# Large_Simon_Says.net
KiCad netlist of a schematic drawn in EAGLE
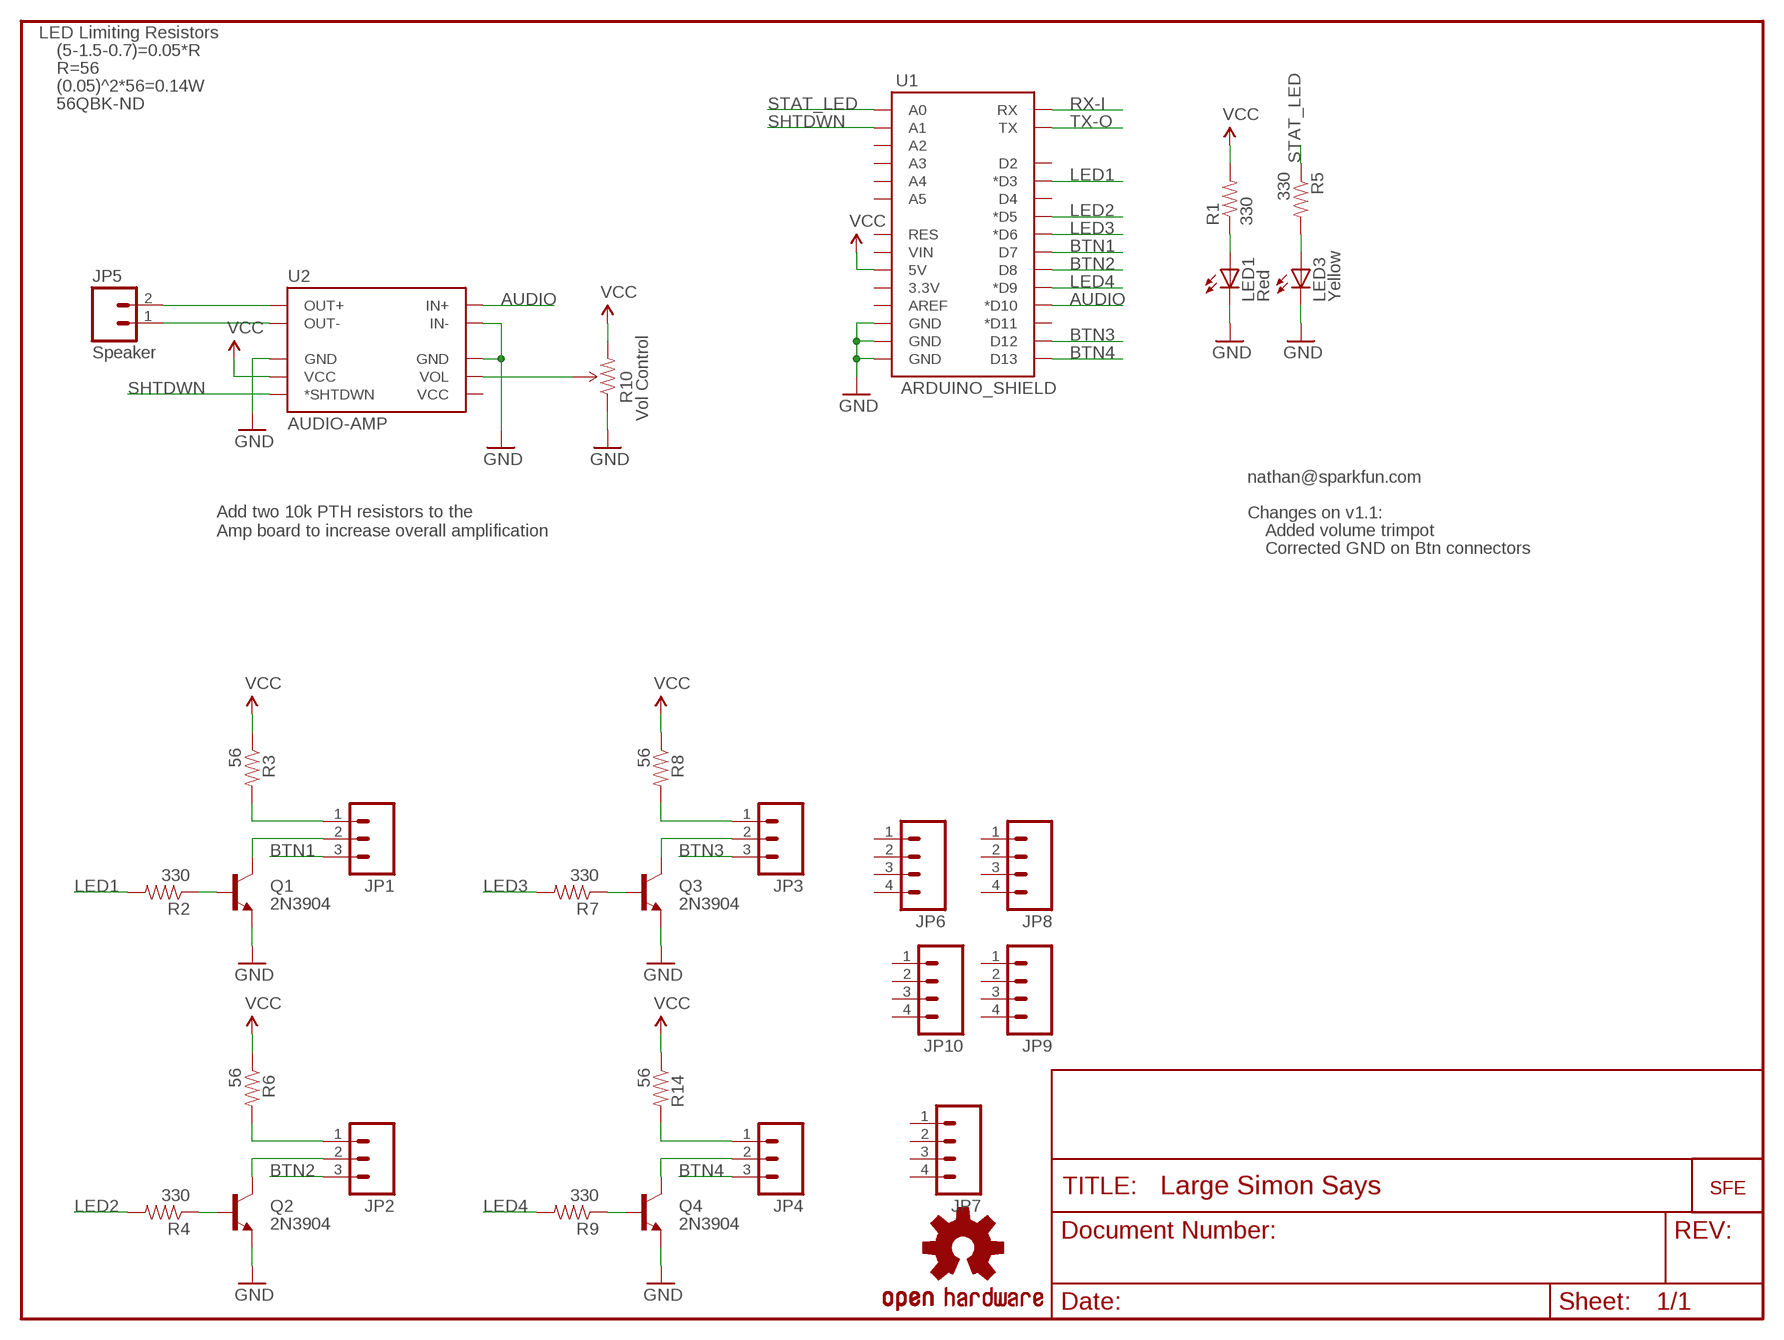
[diagram p0: schematic, sheet 1]

(export (version "E")
  (design (tool "Eeschema 10.0.6"))
  (components
    (comp (ref "JP1")
      (value "M03JST-PTH-VERT")
      (footprint "eagle-import:JST-3-PTH-VERT")
      (libsource (lib "eagle-import") (part "M03JST-PTH-VERT"))
    )
    (comp (ref "JP2")
      (value "M03JST-PTH-VERT")
      (footprint "eagle-import:JST-3-PTH-VERT")
      (libsource (lib "eagle-import") (part "M03JST-PTH-VERT"))
    )
    (comp (ref "JP3")
      (value "M03JST-PTH-VERT")
      (footprint "eagle-import:JST-3-PTH-VERT")
      (libsource (lib "eagle-import") (part "M03JST-PTH-VERT"))
    )
    (comp (ref "JP4")
      (value "M03JST-PTH-VERT")
      (footprint "eagle-import:JST-3-PTH-VERT")
      (libsource (lib "eagle-import") (part "M03JST-PTH-VERT"))
    )
    (comp (ref "JP5")
      (value "Speaker")
      (footprint "eagle-import:JST-2-PTH")
      (libsource (lib "eagle-import") (part "M02JST-PTH-2"))
    )
    (comp (ref "JP6")
      (value "M04JST-PTH")
      (footprint "eagle-import:JST-4-PTH")
      (libsource (lib "eagle-import") (part "M04JST-PTH"))
    )
    (comp (ref "JP7")
      (value "M04JST-PTH")
      (footprint "eagle-import:JST-4-PTH")
      (libsource (lib "eagle-import") (part "M04JST-PTH"))
    )
    (comp (ref "JP8")
      (value "M04JST-PTH")
      (footprint "eagle-import:JST-4-PTH")
      (libsource (lib "eagle-import") (part "M04JST-PTH"))
    )
    (comp (ref "JP9")
      (value "M04JST-PTH")
      (footprint "eagle-import:JST-4-PTH")
      (libsource (lib "eagle-import") (part "M04JST-PTH"))
    )
    (comp (ref "JP10")
      (value "M04JST-PTH")
      (footprint "eagle-import:JST-4-PTH")
      (libsource (lib "eagle-import") (part "M04JST-PTH"))
    )
    (comp (ref "LED1")
      (value "Red")
      (footprint "eagle-import:LED5MM")
      (libsource (lib "eagle-import") (part "LED5MM"))
    )
    (comp (ref "LED3")
      (value "Yellow")
      (footprint "eagle-import:LED5MM")
      (libsource (lib "eagle-import") (part "LED5MM"))
    )
    (comp (ref "Q1")
      (value "2N3904")
      (footprint "eagle-import:TO-92")
      (libsource (lib "eagle-import") (part "TRANSISTOR_NPNTO92"))
    )
    (comp (ref "Q2")
      (value "2N3904")
      (footprint "eagle-import:TO-92")
      (libsource (lib "eagle-import") (part "TRANSISTOR_NPNTO92"))
    )
    (comp (ref "Q3")
      (value "2N3904")
      (footprint "eagle-import:TO-92")
      (libsource (lib "eagle-import") (part "TRANSISTOR_NPNTO92"))
    )
    (comp (ref "Q4")
      (value "2N3904")
      (footprint "eagle-import:TO-92")
      (libsource (lib "eagle-import") (part "TRANSISTOR_NPNTO92"))
    )
    (comp (ref "R1")
      (value "330")
      (footprint "eagle-import:AXIAL-0.3")
      (libsource (lib "eagle-import") (part "RESISTORAXIAL-0.3"))
    )
    (comp (ref "R2")
      (value "330")
      (footprint "eagle-import:AXIAL-0.3")
      (libsource (lib "eagle-import") (part "RESISTORAXIAL-0.3"))
    )
    (comp (ref "R3")
      (value "56")
      (footprint "eagle-import:AXIAL-0.3")
      (libsource (lib "eagle-import") (part "RESISTORAXIAL-0.3"))
    )
    (comp (ref "R4")
      (value "330")
      (footprint "eagle-import:AXIAL-0.3")
      (libsource (lib "eagle-import") (part "RESISTORAXIAL-0.3"))
    )
    (comp (ref "R5")
      (value "330")
      (footprint "eagle-import:AXIAL-0.3")
      (libsource (lib "eagle-import") (part "RESISTORAXIAL-0.3"))
    )
    (comp (ref "R6")
      (value "56")
      (footprint "eagle-import:AXIAL-0.3")
      (libsource (lib "eagle-import") (part "RESISTORAXIAL-0.3"))
    )
    (comp (ref "R7")
      (value "330")
      (footprint "eagle-import:AXIAL-0.3")
      (libsource (lib "eagle-import") (part "RESISTORAXIAL-0.3"))
    )
    (comp (ref "R8")
      (value "56")
      (footprint "eagle-import:AXIAL-0.3")
      (libsource (lib "eagle-import") (part "RESISTORAXIAL-0.3"))
    )
    (comp (ref "R9")
      (value "330")
      (footprint "eagle-import:AXIAL-0.3")
      (libsource (lib "eagle-import") (part "RESISTORAXIAL-0.3"))
    )
    (comp (ref "R10")
      (value "Vol Control")
      (footprint "eagle-import:3386U")
      (libsource (lib "eagle-import") (part "TRIMPOT-PTH-KNOB"))
    )
    (comp (ref "R14")
      (value "56")
      (footprint "eagle-import:AXIAL-0.3")
      (libsource (lib "eagle-import") (part "RESISTORAXIAL-0.3"))
    )
    (comp (ref "U$1")
      (value "LOGO-SFENEW")
      (footprint "eagle-import:SFE-NEW-WEBLOGO")
      (libsource (lib "eagle-import") (part "LOGO-SFENEW"))
    )
    (comp (ref "U$3")
      (value "OSHW-LOGOS")
      (footprint "eagle-import:OSHW-LOGO-S")
      (libsource (lib "eagle-import") (part "OSHW-LOGOS"))
    )
    (comp (ref "U1")
      (value "ARDUINO_SHIELD")
      (footprint "eagle-import:DUEMILANOVE_SHIELD_NOHOLES")
      (libsource (lib "eagle-import") (part "ARDUINO_SHIELDNOHOLES"))
    )
    (comp (ref "U2")
      (value "AUDIO-AMP")
      (footprint "eagle-import:AUDIO-AMP-MONO")
      (libsource (lib "eagle-import") (part "AUDIO-AMP-MONODIP"))
    )
  )
  (nets
    (net (code "1") (name "/AUDIO") (class "Default")
      (node (ref "U1") (pin "D10") (pinfunction "*D10_D10") (pintype "bidirectional"))
      (node (ref "U2") (pin "IN+") (pinfunction "IN+_IN+") (pintype "bidirectional"))
    )
    (net (code "2") (name "/BTN1") (class "Default")
      (node (ref "JP1") (pin "3") (pinfunction "3_3") (pintype "passive"))
      (node (ref "U1") (pin "D7") (pinfunction "D7_D7") (pintype "bidirectional"))
    )
    (net (code "3") (name "/BTN2") (class "Default")
      (node (ref "JP2") (pin "3") (pinfunction "3_3") (pintype "passive"))
      (node (ref "U1") (pin "D8") (pinfunction "D8_D8") (pintype "bidirectional"))
    )
    (net (code "4") (name "/BTN3") (class "Default")
      (node (ref "JP3") (pin "3") (pinfunction "3_3") (pintype "passive"))
      (node (ref "U1") (pin "D12") (pinfunction "D12_D12") (pintype "bidirectional"))
    )
    (net (code "5") (name "/BTN4") (class "Default")
      (node (ref "JP4") (pin "3") (pinfunction "3_3") (pintype "passive"))
      (node (ref "U1") (pin "D13") (pinfunction "D13_D13") (pintype "bidirectional"))
    )
    (net (code "6") (name "/LED1") (class "Default")
      (node (ref "R2") (pin "P$2") (pinfunction "2_P$2") (pintype "passive"))
      (node (ref "U1") (pin "D3") (pinfunction "*D3_D3") (pintype "bidirectional"))
    )
    (net (code "7") (name "/LED2") (class "Default")
      (node (ref "R4") (pin "P$2") (pinfunction "2_P$2") (pintype "passive"))
      (node (ref "U1") (pin "D5") (pinfunction "*D5_D5") (pintype "bidirectional"))
    )
    (net (code "8") (name "/LED3") (class "Default")
      (node (ref "R7") (pin "P$2") (pinfunction "2_P$2") (pintype "passive"))
      (node (ref "U1") (pin "D6") (pinfunction "*D6_D6") (pintype "bidirectional"))
    )
    (net (code "9") (name "/LED4") (class "Default")
      (node (ref "R9") (pin "P$2") (pinfunction "2_P$2") (pintype "passive"))
      (node (ref "U1") (pin "D9") (pinfunction "*D9_D9") (pintype "bidirectional"))
    )
    (net (code "10") (name "/RX-I") (class "Default")
      (node (ref "U1") (pin "RX") (pinfunction "RX_RX") (pintype "bidirectional"))
    )
    (net (code "11") (name "/SHTDWN") (class "Default")
      (node (ref "U1") (pin "A1") (pinfunction "A1_A1") (pintype "bidirectional"))
      (node (ref "U2") (pin "S") (pinfunction "*SHTDWN_S") (pintype "bidirectional"))
    )
    (net (code "12") (name "/STAT_LED") (class "Default")
      (node (ref "R5") (pin "P$1") (pinfunction "1_P$1") (pintype "passive"))
      (node (ref "U1") (pin "A0") (pinfunction "A0_A0") (pintype "bidirectional"))
    )
    (net (code "13") (name "/TX-O") (class "Default")
      (node (ref "U1") (pin "TX") (pinfunction "TX_TX") (pintype "bidirectional"))
    )
    (net (code "14") (name "GND") (class "Default")
      (node (ref "LED1") (pin "K") (pinfunction "C_K") (pintype "passive"))
      (node (ref "LED3") (pin "K") (pinfunction "C_K") (pintype "passive"))
      (node (ref "Q1") (pin "1") (pinfunction "E_1") (pintype "passive"))
      (node (ref "Q2") (pin "1") (pinfunction "E_1") (pintype "passive"))
      (node (ref "Q3") (pin "1") (pinfunction "E_1") (pintype "passive"))
      (node (ref "Q4") (pin "1") (pinfunction "E_1") (pintype "passive"))
      (node (ref "R10") (pin "1") (pinfunction "CCW_1") (pintype "passive"))
      (node (ref "U1") (pin "GND@0") (pinfunction "GND_GND@0") (pintype "bidirectional"))
      (node (ref "U1") (pin "GND@1") (pinfunction "GND_GND@1") (pintype "bidirectional"))
      (node (ref "U1") (pin "GND@2") (pinfunction "GND_GND@2") (pintype "bidirectional"))
      (node (ref "U2") (pin "IN-") (pinfunction "IN-_IN-") (pintype "bidirectional"))
      (node (ref "U2") (pin "PWR-") (pinfunction "GND_PWR-") (pintype "bidirectional"))
      (node (ref "U2") (pin "VOL-") (pinfunction "GND_VOL-") (pintype "bidirectional"))
    )
    (net (code "15") (name "Net-(JP5-Pad1)") (class "Default")
      (node (ref "JP5") (pin "1") (pinfunction "1_1") (pintype "passive"))
      (node (ref "U2") (pin "OUT-") (pinfunction "OUT-_OUT-") (pintype "bidirectional"))
    )
    (net (code "16") (name "Net-(JP5-Pad2)") (class "Default")
      (node (ref "JP5") (pin "2") (pinfunction "2_2") (pintype "passive"))
      (node (ref "U2") (pin "OUT+") (pinfunction "OUT+_OUT+") (pintype "bidirectional"))
    )
    (net (code "17") (name "Net-(Q1-B)") (class "Default")
      (node (ref "Q1") (pin "2") (pinfunction "B_2") (pintype "passive"))
      (node (ref "R2") (pin "P$1") (pinfunction "1_P$1") (pintype "passive"))
    )
    (net (code "18") (name "Net-(Q1-C)") (class "Default")
      (node (ref "JP1") (pin "2") (pinfunction "2_2") (pintype "passive"))
      (node (ref "Q1") (pin "3") (pinfunction "C_3") (pintype "passive"))
    )
    (net (code "19") (name "Net-(Q2-B)") (class "Default")
      (node (ref "Q2") (pin "2") (pinfunction "B_2") (pintype "passive"))
      (node (ref "R4") (pin "P$1") (pinfunction "1_P$1") (pintype "passive"))
    )
    (net (code "20") (name "Net-(Q2-C)") (class "Default")
      (node (ref "JP2") (pin "2") (pinfunction "2_2") (pintype "passive"))
      (node (ref "Q2") (pin "3") (pinfunction "C_3") (pintype "passive"))
    )
    (net (code "21") (name "Net-(Q3-B)") (class "Default")
      (node (ref "Q3") (pin "2") (pinfunction "B_2") (pintype "passive"))
      (node (ref "R7") (pin "P$1") (pinfunction "1_P$1") (pintype "passive"))
    )
    (net (code "22") (name "Net-(Q3-C)") (class "Default")
      (node (ref "JP3") (pin "2") (pinfunction "2_2") (pintype "passive"))
      (node (ref "Q3") (pin "3") (pinfunction "C_3") (pintype "passive"))
    )
    (net (code "23") (name "Net-(Q4-B)") (class "Default")
      (node (ref "Q4") (pin "2") (pinfunction "B_2") (pintype "passive"))
      (node (ref "R9") (pin "P$1") (pinfunction "1_P$1") (pintype "passive"))
    )
    (net (code "24") (name "Net-(Q4-C)") (class "Default")
      (node (ref "JP4") (pin "2") (pinfunction "2_2") (pintype "passive"))
      (node (ref "Q4") (pin "3") (pinfunction "C_3") (pintype "passive"))
    )
    (net (code "25") (name "Net-(R1-1)") (class "Default")
      (node (ref "LED1") (pin "A") (pinfunction "A_A") (pintype "passive"))
      (node (ref "R1") (pin "P$1") (pinfunction "1_P$1") (pintype "passive"))
    )
    (net (code "26") (name "Net-(R3-2)") (class "Default")
      (node (ref "JP1") (pin "1") (pinfunction "1_1") (pintype "passive"))
      (node (ref "R3") (pin "P$2") (pinfunction "2_P$2") (pintype "passive"))
    )
    (net (code "27") (name "Net-(R5-2)") (class "Default")
      (node (ref "LED3") (pin "A") (pinfunction "A_A") (pintype "passive"))
      (node (ref "R5") (pin "P$2") (pinfunction "2_P$2") (pintype "passive"))
    )
    (net (code "28") (name "Net-(R6-2)") (class "Default")
      (node (ref "JP2") (pin "1") (pinfunction "1_1") (pintype "passive"))
      (node (ref "R6") (pin "P$2") (pinfunction "2_P$2") (pintype "passive"))
    )
    (net (code "29") (name "Net-(R8-2)") (class "Default")
      (node (ref "JP3") (pin "1") (pinfunction "1_1") (pintype "passive"))
      (node (ref "R8") (pin "P$2") (pinfunction "2_P$2") (pintype "passive"))
    )
    (net (code "30") (name "Net-(R10-WIPER)") (class "Default")
      (node (ref "R10") (pin "2") (pinfunction "WIPER_2") (pintype "passive"))
      (node (ref "U2") (pin "VOL") (pinfunction "VOL_VOL") (pintype "bidirectional"))
    )
    (net (code "31") (name "Net-(R14-2)") (class "Default")
      (node (ref "JP4") (pin "1") (pinfunction "1_1") (pintype "passive"))
      (node (ref "R14") (pin "P$2") (pinfunction "2_P$2") (pintype "passive"))
    )
    (net (code "32") (name "VCC") (class "Default")
      (node (ref "R1") (pin "P$2") (pinfunction "2_P$2") (pintype "passive"))
      (node (ref "R10") (pin "3") (pinfunction "CW_3") (pintype "passive"))
      (node (ref "R14") (pin "P$1") (pinfunction "1_P$1") (pintype "passive"))
      (node (ref "R3") (pin "P$1") (pinfunction "1_P$1") (pintype "passive"))
      (node (ref "R6") (pin "P$1") (pinfunction "1_P$1") (pintype "passive"))
      (node (ref "R8") (pin "P$1") (pinfunction "1_P$1") (pintype "passive"))
      (node (ref "U1") (pin "5V") (pinfunction "5V_5V") (pintype "bidirectional"))
      (node (ref "U2") (pin "PWR+") (pinfunction "VCC_PWR+") (pintype "bidirectional"))
    )
    (net (code "33") (name "unconnected-(JP6-Pad1)") (class "Default")
      (node (ref "JP6") (pin "1") (pinfunction "1_1") (pintype "passive"))
    )
    (net (code "34") (name "unconnected-(JP6-Pad2)") (class "Default")
      (node (ref "JP6") (pin "2") (pinfunction "2_2") (pintype "passive"))
    )
    (net (code "35") (name "unconnected-(JP6-Pad3)") (class "Default")
      (node (ref "JP6") (pin "3") (pinfunction "3_3") (pintype "passive"))
    )
    (net (code "36") (name "unconnected-(JP6-Pad4)") (class "Default")
      (node (ref "JP6") (pin "4") (pinfunction "4_4") (pintype "passive"))
    )
    (net (code "37") (name "unconnected-(JP7-Pad1)") (class "Default")
      (node (ref "JP7") (pin "1") (pinfunction "1_1") (pintype "passive"))
    )
    (net (code "38") (name "unconnected-(JP7-Pad2)") (class "Default")
      (node (ref "JP7") (pin "2") (pinfunction "2_2") (pintype "passive"))
    )
    (net (code "39") (name "unconnected-(JP7-Pad3)") (class "Default")
      (node (ref "JP7") (pin "3") (pinfunction "3_3") (pintype "passive"))
    )
    (net (code "40") (name "unconnected-(JP7-Pad4)") (class "Default")
      (node (ref "JP7") (pin "4") (pinfunction "4_4") (pintype "passive"))
    )
    (net (code "41") (name "unconnected-(JP8-Pad1)") (class "Default")
      (node (ref "JP8") (pin "1") (pinfunction "1_1") (pintype "passive"))
    )
    (net (code "42") (name "unconnected-(JP8-Pad2)") (class "Default")
      (node (ref "JP8") (pin "2") (pinfunction "2_2") (pintype "passive"))
    )
    (net (code "43") (name "unconnected-(JP8-Pad3)") (class "Default")
      (node (ref "JP8") (pin "3") (pinfunction "3_3") (pintype "passive"))
    )
    (net (code "44") (name "unconnected-(JP8-Pad4)") (class "Default")
      (node (ref "JP8") (pin "4") (pinfunction "4_4") (pintype "passive"))
    )
    (net (code "45") (name "unconnected-(JP9-Pad1)") (class "Default")
      (node (ref "JP9") (pin "1") (pinfunction "1_1") (pintype "passive"))
    )
    (net (code "46") (name "unconnected-(JP9-Pad2)") (class "Default")
      (node (ref "JP9") (pin "2") (pinfunction "2_2") (pintype "passive"))
    )
    (net (code "47") (name "unconnected-(JP9-Pad3)") (class "Default")
      (node (ref "JP9") (pin "3") (pinfunction "3_3") (pintype "passive"))
    )
    (net (code "48") (name "unconnected-(JP9-Pad4)") (class "Default")
      (node (ref "JP9") (pin "4") (pinfunction "4_4") (pintype "passive"))
    )
    (net (code "49") (name "unconnected-(JP10-Pad1)") (class "Default")
      (node (ref "JP10") (pin "1") (pinfunction "1_1") (pintype "passive"))
    )
    (net (code "50") (name "unconnected-(JP10-Pad2)") (class "Default")
      (node (ref "JP10") (pin "2") (pinfunction "2_2") (pintype "passive"))
    )
    (net (code "51") (name "unconnected-(JP10-Pad3)") (class "Default")
      (node (ref "JP10") (pin "3") (pinfunction "3_3") (pintype "passive"))
    )
    (net (code "52") (name "unconnected-(JP10-Pad4)") (class "Default")
      (node (ref "JP10") (pin "4") (pinfunction "4_4") (pintype "passive"))
    )
    (net (code "53") (name "unconnected-(U1-*D11-PadD11)") (class "Default")
      (node (ref "U1") (pin "D11") (pinfunction "*D11_D11") (pintype "bidirectional"))
    )
    (net (code "54") (name "unconnected-(U1-Pad3.3V)") (class "Default")
      (node (ref "U1") (pin "3.3V") (pinfunction "3.3V_3.3V") (pintype "bidirectional"))
    )
    (net (code "55") (name "unconnected-(U1-PadA2)") (class "Default")
      (node (ref "U1") (pin "A2") (pinfunction "A2_A2") (pintype "bidirectional"))
    )
    (net (code "56") (name "unconnected-(U1-PadA3)") (class "Default")
      (node (ref "U1") (pin "A3") (pinfunction "A3_A3") (pintype "bidirectional"))
    )
    (net (code "57") (name "unconnected-(U1-PadA4)") (class "Default")
      (node (ref "U1") (pin "A4") (pinfunction "A4_A4") (pintype "bidirectional"))
    )
    (net (code "58") (name "unconnected-(U1-PadA5)") (class "Default")
      (node (ref "U1") (pin "A5") (pinfunction "A5_A5") (pintype "bidirectional"))
    )
    (net (code "59") (name "unconnected-(U1-PadAREF)") (class "Default")
      (node (ref "U1") (pin "AREF") (pinfunction "AREF_AREF") (pintype "bidirectional"))
    )
    (net (code "60") (name "unconnected-(U1-PadD2)") (class "Default")
      (node (ref "U1") (pin "D2") (pinfunction "D2_D2") (pintype "bidirectional"))
    )
    (net (code "61") (name "unconnected-(U1-PadD4)") (class "Default")
      (node (ref "U1") (pin "D4") (pinfunction "D4_D4") (pintype "bidirectional"))
    )
    (net (code "62") (name "unconnected-(U1-PadRES)") (class "Default")
      (node (ref "U1") (pin "RES") (pinfunction "RES_RES") (pintype "bidirectional"))
    )
    (net (code "63") (name "unconnected-(U1-PadVIN)") (class "Default")
      (node (ref "U1") (pin "VIN") (pinfunction "VIN_VIN") (pintype "bidirectional"))
    )
    (net (code "64") (name "unconnected-(U2-VCC-PadVOL+)") (class "Default")
      (node (ref "U2") (pin "VOL+") (pinfunction "VCC_VOL+") (pintype "bidirectional"))
    )
  )
)
